# Whale_Lamp-base.net
KiCad netlist of a schematic drawn in EAGLE
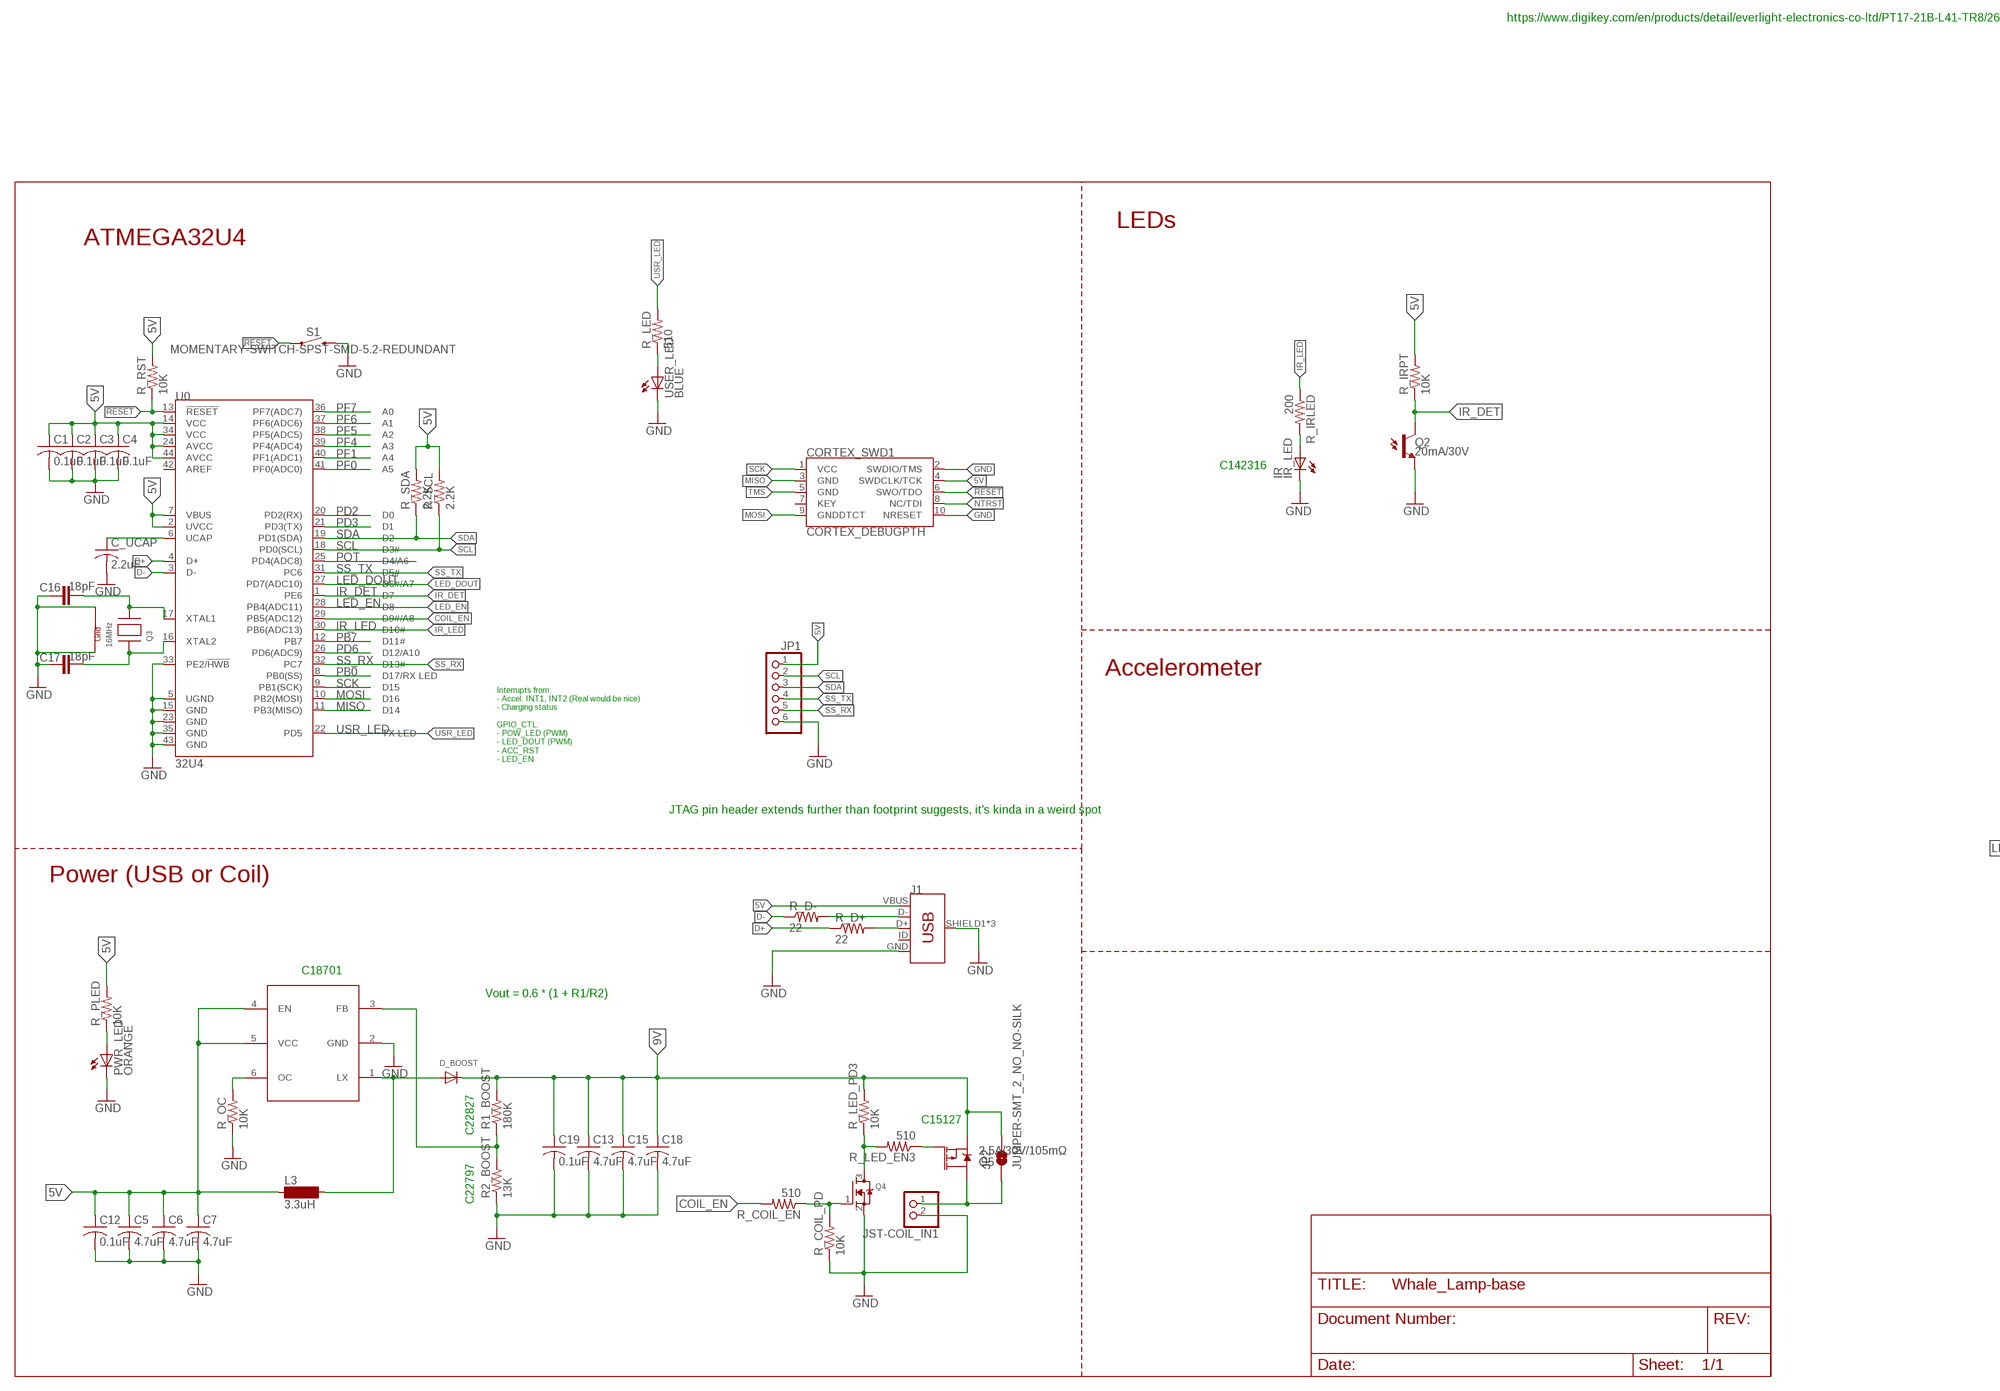
[diagram p0: schematic, sheet 1, part 1 of 2]
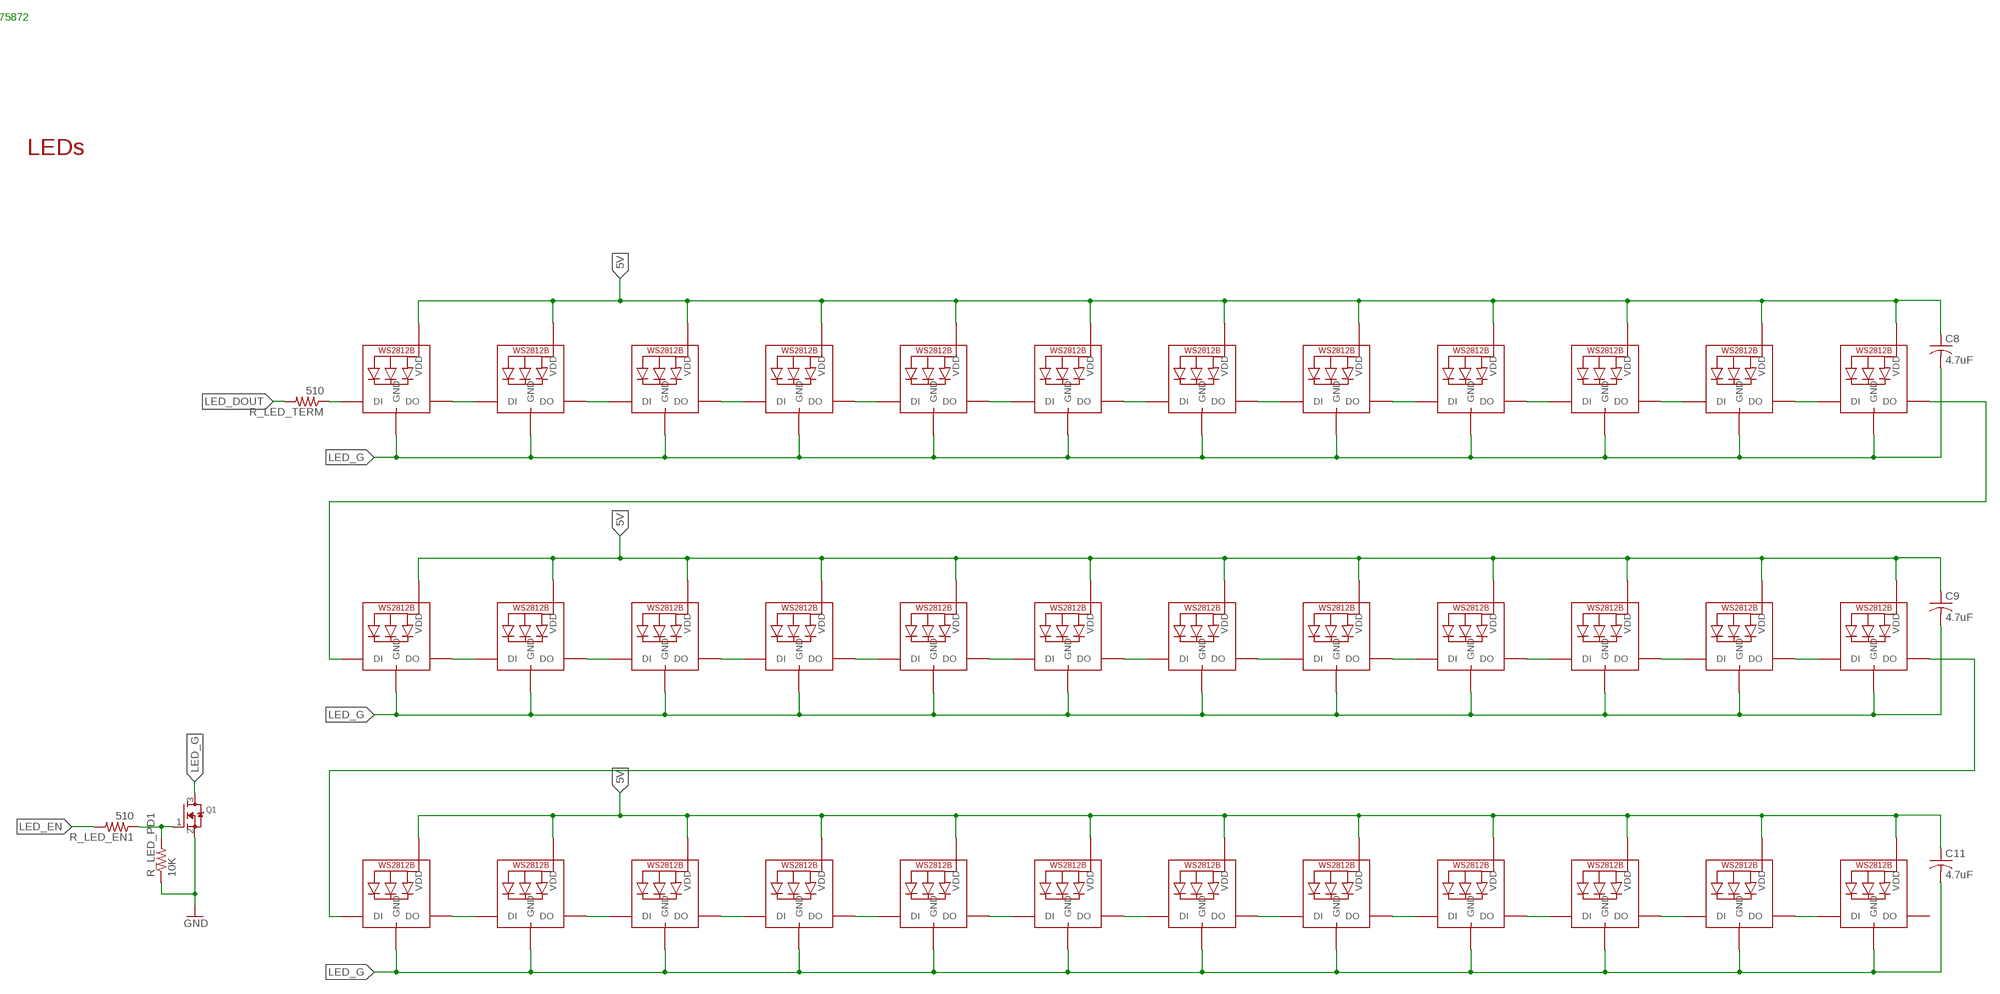
[diagram p1: schematic, sheet 1, part 2 of 2]

(export (version "E")
  (design (tool "Eeschema 10.0.6"))
  (components
    (comp (ref "C1")
      (value "0.1uF")
      (footprint "eagle-import:C0402")
      (libsource (lib "eagle-import") (part "C-USC0402"))
    )
    (comp (ref "C2")
      (value "0.1uF")
      (footprint "eagle-import:C0402")
      (libsource (lib "eagle-import") (part "C-USC0402"))
    )
    (comp (ref "C3")
      (value "0.1uF")
      (footprint "eagle-import:C0402")
      (libsource (lib "eagle-import") (part "C-USC0402"))
    )
    (comp (ref "C4")
      (value "0.1uF")
      (footprint "eagle-import:C0402")
      (libsource (lib "eagle-import") (part "C-USC0402"))
    )
    (comp (ref "C5")
      (value "4.7uF")
      (footprint "eagle-import:C0603")
      (libsource (lib "eagle-import") (part "C-USC0603"))
    )
    (comp (ref "C6")
      (value "4.7uF")
      (footprint "eagle-import:C0603")
      (libsource (lib "eagle-import") (part "C-USC0603"))
    )
    (comp (ref "C7")
      (value "4.7uF")
      (footprint "eagle-import:C0603")
      (libsource (lib "eagle-import") (part "C-USC0603"))
    )
    (comp (ref "C8")
      (value "4.7uF")
      (footprint "eagle-import:C0603")
      (libsource (lib "eagle-import") (part "C-USC0603"))
    )
    (comp (ref "C9")
      (value "4.7uF")
      (footprint "eagle-import:C0603")
      (libsource (lib "eagle-import") (part "C-USC0603"))
    )
    (comp (ref "C11")
      (value "4.7uF")
      (footprint "eagle-import:C0603")
      (libsource (lib "eagle-import") (part "C-USC0603"))
    )
    (comp (ref "C12")
      (value "0.1uF")
      (footprint "eagle-import:C0402")
      (libsource (lib "eagle-import") (part "C-USC0402"))
    )
    (comp (ref "C13")
      (value "4.7uF")
      (footprint "eagle-import:C0603")
      (libsource (lib "eagle-import") (part "C-USC0603"))
    )
    (comp (ref "C15")
      (value "4.7uF")
      (footprint "eagle-import:C0603")
      (libsource (lib "eagle-import") (part "C-USC0603"))
    )
    (comp (ref "C16")
      (value "18pF")
      (footprint "eagle-import:0402-CAP")
      (libsource (lib "eagle-import") (part "CAP0402-CAP"))
    )
    (comp (ref "C17")
      (value "18pF")
      (footprint "eagle-import:0402-CAP")
      (libsource (lib "eagle-import") (part "CAP0402-CAP"))
    )
    (comp (ref "C18")
      (value "4.7uF")
      (footprint "eagle-import:C0603")
      (libsource (lib "eagle-import") (part "C-USC0603"))
    )
    (comp (ref "C19")
      (value "0.1uF")
      (footprint "eagle-import:C0402")
      (libsource (lib "eagle-import") (part "C-USC0402"))
    )
    (comp (ref "CORTEX_SWD1")
      (value "CORTEX_DEBUGPTH")
      (footprint "eagle-import:2X5-PTH-1.27MM")
      (libsource (lib "eagle-import") (part "CORTEX_DEBUGPTH"))
    )
    (comp (ref "C_UCAP")
      (value "2.2uF")
      (footprint "eagle-import:C0603")
      (libsource (lib "eagle-import") (part "C-USC0603"))
    )
    (comp (ref "D_BOOST")
      (value "DIODESOD-123")
      (footprint "eagle-import:SOD-123")
      (libsource (lib "eagle-import") (part "DIODESOD-123"))
    )
    (comp (ref "FP6291")
      (value "FP6291")
      (footprint "eagle-import:SOT23-6L")
      (libsource (lib "eagle-import") (part "FP6291"))
    )
    (comp (ref "IR_LED")
      (value "IR")
      (footprint "eagle-import:CHIPLED_0603")
      (libsource (lib "eagle-import") (part "LEDCHIPLED_0603"))
    )
    (comp (ref "J1")
      (value "USB_MICRO-B_FEMALE-SMT")
      (footprint "eagle-import:USB-B-MICRO-SMD")
      (libsource (lib "eagle-import") (part "USB_MICRO-B_FEMALE-SMT"))
    )
    (comp (ref "JP1")
      (value "PINHD-1X6")
      (footprint "eagle-import:1X06")
      (libsource (lib "eagle-import") (part "PINHD-1X6"))
    )
    (comp (ref "JP2")
      (value "JUMPER-SMT_2_NO_NO-SILK")
      (footprint "eagle-import:SMT-JUMPER_2_NO_NO-SILK")
      (libsource (lib "eagle-import") (part "JUMPER-SMT_2_NO_NO-SILK"))
    )
    (comp (ref "JST-COIL_IN1")
      (value "JST_2PIN-THM-RA")
      (footprint "eagle-import:JST-PH-2-THM-RA")
      (libsource (lib "eagle-import") (part "JST_2PIN-THM-RA"))
    )
    (comp (ref "L3")
      (value "3.3uH")
      (footprint "eagle-import:MS50")
      (libsource (lib "eagle-import") (part "MS50"))
    )
    (comp (ref "LED1")
      (value "WS2812B_5050N")
      (footprint "eagle-import:WS2812B-NARROW")
      (libsource (lib "eagle-import") (part "WS2812B_5050N"))
    )
    (comp (ref "LED2")
      (value "WS2812B_5050N")
      (footprint "eagle-import:WS2812B-NARROW")
      (libsource (lib "eagle-import") (part "WS2812B_5050N"))
    )
    (comp (ref "LED3")
      (value "WS2812B_5050N")
      (footprint "eagle-import:WS2812B-NARROW")
      (libsource (lib "eagle-import") (part "WS2812B_5050N"))
    )
    (comp (ref "LED4")
      (value "WS2812B_5050N")
      (footprint "eagle-import:WS2812B-NARROW")
      (libsource (lib "eagle-import") (part "WS2812B_5050N"))
    )
    (comp (ref "LED5")
      (value "WS2812B_5050N")
      (footprint "eagle-import:WS2812B-NARROW")
      (libsource (lib "eagle-import") (part "WS2812B_5050N"))
    )
    (comp (ref "LED6")
      (value "WS2812B_5050N")
      (footprint "eagle-import:WS2812B-NARROW")
      (libsource (lib "eagle-import") (part "WS2812B_5050N"))
    )
    (comp (ref "LED7")
      (value "WS2812B_5050N")
      (footprint "eagle-import:WS2812B-NARROW")
      (libsource (lib "eagle-import") (part "WS2812B_5050N"))
    )
    (comp (ref "LED8")
      (value "WS2812B_5050N")
      (footprint "eagle-import:WS2812B-NARROW")
      (libsource (lib "eagle-import") (part "WS2812B_5050N"))
    )
    (comp (ref "LED9")
      (value "WS2812B_5050N")
      (footprint "eagle-import:WS2812B-NARROW")
      (libsource (lib "eagle-import") (part "WS2812B_5050N"))
    )
    (comp (ref "LED10")
      (value "WS2812B_5050N")
      (footprint "eagle-import:WS2812B-NARROW")
      (libsource (lib "eagle-import") (part "WS2812B_5050N"))
    )
    (comp (ref "LED11")
      (value "WS2812B_5050N")
      (footprint "eagle-import:WS2812B-NARROW")
      (libsource (lib "eagle-import") (part "WS2812B_5050N"))
    )
    (comp (ref "LED12")
      (value "WS2812B_5050N")
      (footprint "eagle-import:WS2812B-NARROW")
      (libsource (lib "eagle-import") (part "WS2812B_5050N"))
    )
    (comp (ref "LED13")
      (value "WS2812B_5050N")
      (footprint "eagle-import:WS2812B-NARROW")
      (libsource (lib "eagle-import") (part "WS2812B_5050N"))
    )
    (comp (ref "LED14")
      (value "WS2812B_5050N")
      (footprint "eagle-import:WS2812B-NARROW")
      (libsource (lib "eagle-import") (part "WS2812B_5050N"))
    )
    (comp (ref "LED15")
      (value "WS2812B_5050N")
      (footprint "eagle-import:WS2812B-NARROW")
      (libsource (lib "eagle-import") (part "WS2812B_5050N"))
    )
    (comp (ref "LED16")
      (value "WS2812B_5050N")
      (footprint "eagle-import:WS2812B-NARROW")
      (libsource (lib "eagle-import") (part "WS2812B_5050N"))
    )
    (comp (ref "LED17")
      (value "WS2812B_5050N")
      (footprint "eagle-import:WS2812B-NARROW")
      (libsource (lib "eagle-import") (part "WS2812B_5050N"))
    )
    (comp (ref "LED18")
      (value "WS2812B_5050N")
      (footprint "eagle-import:WS2812B-NARROW")
      (libsource (lib "eagle-import") (part "WS2812B_5050N"))
    )
    (comp (ref "LED19")
      (value "WS2812B_5050N")
      (footprint "eagle-import:WS2812B-NARROW")
      (libsource (lib "eagle-import") (part "WS2812B_5050N"))
    )
    (comp (ref "LED20")
      (value "WS2812B_5050N")
      (footprint "eagle-import:WS2812B-NARROW")
      (libsource (lib "eagle-import") (part "WS2812B_5050N"))
    )
    (comp (ref "LED21")
      (value "WS2812B_5050N")
      (footprint "eagle-import:WS2812B-NARROW")
      (libsource (lib "eagle-import") (part "WS2812B_5050N"))
    )
    (comp (ref "LED22")
      (value "WS2812B_5050N")
      (footprint "eagle-import:WS2812B-NARROW")
      (libsource (lib "eagle-import") (part "WS2812B_5050N"))
    )
    (comp (ref "LED23")
      (value "WS2812B_5050N")
      (footprint "eagle-import:WS2812B-NARROW")
      (libsource (lib "eagle-import") (part "WS2812B_5050N"))
    )
    (comp (ref "LED24")
      (value "WS2812B_5050N")
      (footprint "eagle-import:WS2812B-NARROW")
      (libsource (lib "eagle-import") (part "WS2812B_5050N"))
    )
    (comp (ref "LED25")
      (value "WS2812B_5050N")
      (footprint "eagle-import:WS2812B-NARROW")
      (libsource (lib "eagle-import") (part "WS2812B_5050N"))
    )
    (comp (ref "LED26")
      (value "WS2812B_5050N")
      (footprint "eagle-import:WS2812B-NARROW")
      (libsource (lib "eagle-import") (part "WS2812B_5050N"))
    )
    (comp (ref "LED27")
      (value "WS2812B_5050N")
      (footprint "eagle-import:WS2812B-NARROW")
      (libsource (lib "eagle-import") (part "WS2812B_5050N"))
    )
    (comp (ref "LED28")
      (value "WS2812B_5050N")
      (footprint "eagle-import:WS2812B-NARROW")
      (libsource (lib "eagle-import") (part "WS2812B_5050N"))
    )
    (comp (ref "LED29")
      (value "WS2812B_5050N")
      (footprint "eagle-import:WS2812B-NARROW")
      (libsource (lib "eagle-import") (part "WS2812B_5050N"))
    )
    (comp (ref "LED30")
      (value "WS2812B_5050N")
      (footprint "eagle-import:WS2812B-NARROW")
      (libsource (lib "eagle-import") (part "WS2812B_5050N"))
    )
    (comp (ref "LED31")
      (value "WS2812B_5050N")
      (footprint "eagle-import:WS2812B-NARROW")
      (libsource (lib "eagle-import") (part "WS2812B_5050N"))
    )
    (comp (ref "LED32")
      (value "WS2812B_5050N")
      (footprint "eagle-import:WS2812B-NARROW")
      (libsource (lib "eagle-import") (part "WS2812B_5050N"))
    )
    (comp (ref "LED33")
      (value "WS2812B_5050N")
      (footprint "eagle-import:WS2812B-NARROW")
      (libsource (lib "eagle-import") (part "WS2812B_5050N"))
    )
    (comp (ref "LED34")
      (value "WS2812B_5050N")
      (footprint "eagle-import:WS2812B-NARROW")
      (libsource (lib "eagle-import") (part "WS2812B_5050N"))
    )
    (comp (ref "LED35")
      (value "WS2812B_5050N")
      (footprint "eagle-import:WS2812B-NARROW")
      (libsource (lib "eagle-import") (part "WS2812B_5050N"))
    )
    (comp (ref "LED36")
      (value "WS2812B_5050N")
      (footprint "eagle-import:WS2812B-NARROW")
      (libsource (lib "eagle-import") (part "WS2812B_5050N"))
    )
    (comp (ref "PWR_LED")
      (value "ORANGE")
      (footprint "eagle-import:CHIPLED_0603")
      (libsource (lib "eagle-import") (part "LEDCHIPLED_0603"))
    )
    (comp (ref "Q1")
      (value "MOSFET-NREFLOW")
      (footprint "eagle-import:SOT23")
      (libsource (lib "eagle-import") (part "MOSFET-NREFLOW"))
    )
    (comp (ref "Q2")
      (value "20mA/30V")
      (footprint "eagle-import:PT17-21C-L41-TR8")
      (libsource (lib "eagle-import") (part "PHOTOTRANSISTORPT17-21C-L41-TR8"))
    )
    (comp (ref "Q3")
      (value "16MHz")
      (footprint "eagle-import:NX3225")
      (libsource (lib "eagle-import") (part "XTAL-4-3225"))
    )
    (comp (ref "Q4")
      (value "MOSFET-NREFLOW")
      (footprint "eagle-import:SOT23")
      (libsource (lib "eagle-import") (part "MOSFET-NREFLOW"))
    )
    (comp (ref "Q5")
      (value "2.5A/30V/105mΩ")
      (footprint "eagle-import:SOT23-3")
      (libsource (lib "eagle-import") (part "MOSFET_PCH-DMG2307L"))
    )
    (comp (ref "R1_BOOST")
      (value "180K")
      (footprint "eagle-import:R0603")
      (libsource (lib "eagle-import") (part "adafruit_420_R-US_R0603"))
    )
    (comp (ref "R2_BOOST")
      (value "13K")
      (footprint "eagle-import:R0603")
      (libsource (lib "eagle-import") (part "adafruit_420_R-US_R0603"))
    )
    (comp (ref "R_COIL_EN")
      (value "510")
      (footprint "eagle-import:R0402")
      (libsource (lib "eagle-import") (part "R-US_R0402"))
    )
    (comp (ref "R_COIL_PD")
      (value "10K")
      (footprint "eagle-import:R0402")
      (libsource (lib "eagle-import") (part "R-US_R0402"))
    )
    (comp (ref "R_D+")
      (value "22")
      (footprint "eagle-import:R0402")
      (libsource (lib "eagle-import") (part "R-US_R0402"))
    )
    (comp (ref "R_D-")
      (value "22")
      (footprint "eagle-import:R0402")
      (libsource (lib "eagle-import") (part "R-US_R0402"))
    )
    (comp (ref "R_IRLED")
      (value "200")
      (footprint "eagle-import:R0603")
      (libsource (lib "eagle-import") (part "R-US_R0603"))
    )
    (comp (ref "R_IRPT")
      (value "10K")
      (footprint "eagle-import:R0402")
      (libsource (lib "eagle-import") (part "R-US_R0402"))
    )
    (comp (ref "R_LED")
      (value "510")
      (footprint "eagle-import:R0402")
      (libsource (lib "eagle-import") (part "R-US_R0402"))
    )
    (comp (ref "R_LED_EN1")
      (value "510")
      (footprint "eagle-import:R0402")
      (libsource (lib "eagle-import") (part "R-US_R0402"))
    )
    (comp (ref "R_LED_EN3")
      (value "510")
      (footprint "eagle-import:R0402")
      (libsource (lib "eagle-import") (part "R-US_R0402"))
    )
    (comp (ref "R_LED_PD1")
      (value "10K")
      (footprint "eagle-import:R0402")
      (libsource (lib "eagle-import") (part "R-US_R0402"))
    )
    (comp (ref "R_LED_PD3")
      (value "10K")
      (footprint "eagle-import:R0402")
      (libsource (lib "eagle-import") (part "R-US_R0402"))
    )
    (comp (ref "R_LED_TERM")
      (value "510")
      (footprint "eagle-import:R0402")
      (libsource (lib "eagle-import") (part "R-US_R0402"))
    )
    (comp (ref "R_OC")
      (value "10K")
      (footprint "eagle-import:R0402")
      (libsource (lib "eagle-import") (part "R-US_R0402"))
    )
    (comp (ref "R_PLED")
      (value "10K")
      (footprint "eagle-import:R0402")
      (libsource (lib "eagle-import") (part "R-US_R0402"))
    )
    (comp (ref "R_RST")
      (value "10K")
      (footprint "eagle-import:R0402")
      (libsource (lib "eagle-import") (part "R-US_R0402"))
    )
    (comp (ref "R_SCL")
      (value "2.2K")
      (footprint "eagle-import:R0402")
      (libsource (lib "eagle-import") (part "R-US_R0402"))
    )
    (comp (ref "R_SDA")
      (value "2.2K")
      (footprint "eagle-import:R0402")
      (libsource (lib "eagle-import") (part "R-US_R0402"))
    )
    (comp (ref "S1")
      (value "MOMENTARY-SWITCH-SPST-SMD-5.2-REDUNDANT")
      (footprint "eagle-import:TACTILE_SWITCH_SMD_5.2MM")
      (libsource (lib "eagle-import") (part "MOMENTARY-SWITCH-SPST-SMD-5.2-REDUNDANT"))
    )
    (comp (ref "U0")
      (value "32U4")
      (footprint "eagle-import:QFN-44")
      (libsource (lib "eagle-import") (part "ATMEGA32U4QFN"))
    )
    (comp (ref "USER_LED")
      (value "BLUE")
      (footprint "eagle-import:CHIPLED_0603")
      (libsource (lib "eagle-import") (part "LEDCHIPLED_0603"))
    )
  )
  (nets
    (net (code "1") (name "/PB0") (class "Default")
      (node (ref "U0") (pin "8") (pinfunction "PB0(SS)_8") (pintype "bidirectional"))
    )
    (net (code "2") (name "/PB7") (class "Default")
      (node (ref "U0") (pin "12") (pinfunction "PB7_12") (pintype "bidirectional"))
    )
    (net (code "3") (name "/PD2") (class "Default")
      (node (ref "U0") (pin "20") (pinfunction "PD2(RX)_20") (pintype "bidirectional"))
    )
    (net (code "4") (name "/PD3") (class "Default")
      (node (ref "U0") (pin "21") (pinfunction "PD3(TX)_21") (pintype "bidirectional"))
    )
    (net (code "5") (name "/PD6") (class "Default")
      (node (ref "U0") (pin "26") (pinfunction "PD6(ADC9)_26") (pintype "bidirectional"))
    )
    (net (code "6") (name "/PF0") (class "Default")
      (node (ref "U0") (pin "41") (pinfunction "PF0(ADC0)_41") (pintype "bidirectional"))
    )
    (net (code "7") (name "/PF1") (class "Default")
      (node (ref "U0") (pin "40") (pinfunction "PF1(ADC1)_40") (pintype "bidirectional"))
    )
    (net (code "8") (name "/PF4") (class "Default")
      (node (ref "U0") (pin "39") (pinfunction "PF4(ADC4)_39") (pintype "bidirectional"))
    )
    (net (code "9") (name "/PF5") (class "Default")
      (node (ref "U0") (pin "38") (pinfunction "PF5(ADC5)_38") (pintype "bidirectional"))
    )
    (net (code "10") (name "/PF6") (class "Default")
      (node (ref "U0") (pin "37") (pinfunction "PF6(ADC6)_37") (pintype "bidirectional"))
    )
    (net (code "11") (name "/PF7") (class "Default")
      (node (ref "U0") (pin "36") (pinfunction "PF7(ADC7)_36") (pintype "bidirectional"))
    )
    (net (code "12") (name "/POT") (class "Default")
      (node (ref "U0") (pin "25") (pinfunction "PD4(ADC8)_25") (pintype "bidirectional"))
    )
    (net (code "13") (name "/~{RESET}") (class "Default")
      (node (ref "CORTEX_SWD1") (pin "6") (pinfunction "SWO/TDO_6") (pintype "bidirectional"))
      (node (ref "R_RST") (pin "1") (pinfunction "1_1") (pintype "passive"))
      (node (ref "S1") (pin "1") (pinfunction "1_1") (pintype "passive"))
      (node (ref "S1") (pin "2") (pinfunction "1_2") (pintype "passive"))
      (node (ref "U0") (pin "13") (pinfunction "~{RESET}_13") (pintype "bidirectional"))
    )
    (net (code "14") (name "5V") (class "Default")
      (node (ref "C1") (pin "1") (pinfunction "1_1") (pintype "passive"))
      (node (ref "C11") (pin "1") (pinfunction "1_1") (pintype "passive"))
      (node (ref "C12") (pin "1") (pinfunction "1_1") (pintype "passive"))
      (node (ref "C2") (pin "1") (pinfunction "1_1") (pintype "passive"))
      (node (ref "C3") (pin "1") (pinfunction "1_1") (pintype "passive"))
      (node (ref "C4") (pin "1") (pinfunction "1_1") (pintype "passive"))
      (node (ref "C5") (pin "1") (pinfunction "1_1") (pintype "passive"))
      (node (ref "C6") (pin "1") (pinfunction "1_1") (pintype "passive"))
      (node (ref "C7") (pin "1") (pinfunction "1_1") (pintype "passive"))
      (node (ref "C8") (pin "1") (pinfunction "1_1") (pintype "passive"))
      (node (ref "C9") (pin "1") (pinfunction "1_1") (pintype "passive"))
      (node (ref "CORTEX_SWD1") (pin "4") (pinfunction "SWDCLK/TCK_4") (pintype "bidirectional"))
      (node (ref "FP6291") (pin "4") (pinfunction "EN_4") (pintype "bidirectional"))
      (node (ref "FP6291") (pin "5") (pinfunction "VCC_5") (pintype "bidirectional"))
      (node (ref "J1") (pin "VBUS") (pinfunction "VBUS_VBUS") (pintype "power_in"))
      (node (ref "JP1") (pin "1") (pinfunction "1_1") (pintype "passive"))
      (node (ref "L3") (pin "1") (pinfunction "1_1") (pintype "passive"))
      (node (ref "LED1") (pin "1-VDD") (pinfunction "VDD_1-VDD") (pintype "power_in"))
      (node (ref "LED10") (pin "1-VDD") (pinfunction "VDD_1-VDD") (pintype "power_in"))
      (node (ref "LED11") (pin "1-VDD") (pinfunction "VDD_1-VDD") (pintype "power_in"))
      (node (ref "LED12") (pin "1-VDD") (pinfunction "VDD_1-VDD") (pintype "power_in"))
      (node (ref "LED13") (pin "1-VDD") (pinfunction "VDD_1-VDD") (pintype "power_in"))
      (node (ref "LED14") (pin "1-VDD") (pinfunction "VDD_1-VDD") (pintype "power_in"))
      (node (ref "LED15") (pin "1-VDD") (pinfunction "VDD_1-VDD") (pintype "power_in"))
      (node (ref "LED16") (pin "1-VDD") (pinfunction "VDD_1-VDD") (pintype "power_in"))
      (node (ref "LED17") (pin "1-VDD") (pinfunction "VDD_1-VDD") (pintype "power_in"))
      (node (ref "LED18") (pin "1-VDD") (pinfunction "VDD_1-VDD") (pintype "power_in"))
      (node (ref "LED19") (pin "1-VDD") (pinfunction "VDD_1-VDD") (pintype "power_in"))
      (node (ref "LED2") (pin "1-VDD") (pinfunction "VDD_1-VDD") (pintype "power_in"))
      (node (ref "LED20") (pin "1-VDD") (pinfunction "VDD_1-VDD") (pintype "power_in"))
      (node (ref "LED21") (pin "1-VDD") (pinfunction "VDD_1-VDD") (pintype "power_in"))
      (node (ref "LED22") (pin "1-VDD") (pinfunction "VDD_1-VDD") (pintype "power_in"))
      (node (ref "LED23") (pin "1-VDD") (pinfunction "VDD_1-VDD") (pintype "power_in"))
      (node (ref "LED24") (pin "1-VDD") (pinfunction "VDD_1-VDD") (pintype "power_in"))
      (node (ref "LED25") (pin "1-VDD") (pinfunction "VDD_1-VDD") (pintype "power_in"))
      (node (ref "LED26") (pin "1-VDD") (pinfunction "VDD_1-VDD") (pintype "power_in"))
      (node (ref "LED27") (pin "1-VDD") (pinfunction "VDD_1-VDD") (pintype "power_in"))
      (node (ref "LED28") (pin "1-VDD") (pinfunction "VDD_1-VDD") (pintype "power_in"))
      (node (ref "LED29") (pin "1-VDD") (pinfunction "VDD_1-VDD") (pintype "power_in"))
      (node (ref "LED3") (pin "1-VDD") (pinfunction "VDD_1-VDD") (pintype "power_in"))
      (node (ref "LED30") (pin "1-VDD") (pinfunction "VDD_1-VDD") (pintype "power_in"))
      (node (ref "LED31") (pin "1-VDD") (pinfunction "VDD_1-VDD") (pintype "power_in"))
      (node (ref "LED32") (pin "1-VDD") (pinfunction "VDD_1-VDD") (pintype "power_in"))
      (node (ref "LED33") (pin "1-VDD") (pinfunction "VDD_1-VDD") (pintype "power_in"))
      (node (ref "LED34") (pin "1-VDD") (pinfunction "VDD_1-VDD") (pintype "power_in"))
      (node (ref "LED35") (pin "1-VDD") (pinfunction "VDD_1-VDD") (pintype "power_in"))
      (node (ref "LED36") (pin "1-VDD") (pinfunction "VDD_1-VDD") (pintype "power_in"))
      (node (ref "LED4") (pin "1-VDD") (pinfunction "VDD_1-VDD") (pintype "power_in"))
      (node (ref "LED5") (pin "1-VDD") (pinfunction "VDD_1-VDD") (pintype "power_in"))
      (node (ref "LED6") (pin "1-VDD") (pinfunction "VDD_1-VDD") (pintype "power_in"))
      (node (ref "LED7") (pin "1-VDD") (pinfunction "VDD_1-VDD") (pintype "power_in"))
      (node (ref "LED8") (pin "1-VDD") (pinfunction "VDD_1-VDD") (pintype "power_in"))
      (node (ref "LED9") (pin "1-VDD") (pinfunction "VDD_1-VDD") (pintype "power_in"))
      (node (ref "R_IRPT") (pin "2") (pinfunction "2_2") (pintype "passive"))
      (node (ref "R_PLED") (pin "2") (pinfunction "2_2") (pintype "passive"))
      (node (ref "R_RST") (pin "2") (pinfunction "2_2") (pintype "passive"))
      (node (ref "R_SCL") (pin "2") (pinfunction "2_2") (pintype "passive"))
      (node (ref "R_SDA") (pin "2") (pinfunction "2_2") (pintype "passive"))
      (node (ref "U0") (pin "14") (pinfunction "VCC_14") (pintype "bidirectional"))
      (node (ref "U0") (pin "2") (pinfunction "UVCC_2") (pintype "bidirectional"))
      (node (ref "U0") (pin "24") (pinfunction "AVCC_24") (pintype "bidirectional"))
      (node (ref "U0") (pin "34") (pinfunction "VCC_34") (pintype "bidirectional"))
      (node (ref "U0") (pin "44") (pinfunction "AVCC_44") (pintype "bidirectional"))
      (node (ref "U0") (pin "7") (pinfunction "VBUS_7") (pintype "bidirectional"))
    )
    (net (code "15") (name "9V") (class "Default")
      (node (ref "C13") (pin "1") (pinfunction "1_1") (pintype "passive"))
      (node (ref "C15") (pin "1") (pinfunction "1_1") (pintype "passive"))
      (node (ref "C18") (pin "1") (pinfunction "1_1") (pintype "passive"))
      (node (ref "C19") (pin "1") (pinfunction "1_1") (pintype "passive"))
      (node (ref "D_BOOST") (pin "C") (pinfunction "C_C") (pintype "passive"))
      (node (ref "JP2") (pin "2") (pinfunction "2_2") (pintype "passive"))
      (node (ref "Q5") (pin "2") (pinfunction "S_2") (pintype "bidirectional"))
      (node (ref "R1_BOOST") (pin "2") (pinfunction "2_2") (pintype "passive"))
      (node (ref "R_LED_PD3") (pin "2") (pinfunction "2_2") (pintype "passive"))
    )
    (net (code "16") (name "COIL_EN") (class "Default")
      (node (ref "R_COIL_EN") (pin "2") (pinfunction "2_2") (pintype "passive"))
      (node (ref "U0") (pin "29") (pinfunction "PB5(ADC12)_29") (pintype "bidirectional"))
    )
    (net (code "17") (name "D+") (class "Default")
      (node (ref "R_D+") (pin "1") (pinfunction "1_1") (pintype "passive"))
      (node (ref "U0") (pin "4") (pinfunction "D+_4") (pintype "bidirectional"))
    )
    (net (code "18") (name "D-") (class "Default")
      (node (ref "R_D-") (pin "1") (pinfunction "1_1") (pintype "passive"))
      (node (ref "U0") (pin "3") (pinfunction "D-_3") (pintype "bidirectional"))
    )
    (net (code "19") (name "GND") (class "Default")
      (node (ref "C1") (pin "2") (pinfunction "2_2") (pintype "passive"))
      (node (ref "C12") (pin "2") (pinfunction "2_2") (pintype "passive"))
      (node (ref "C13") (pin "2") (pinfunction "2_2") (pintype "passive"))
      (node (ref "C15") (pin "2") (pinfunction "2_2") (pintype "passive"))
      (node (ref "C16") (pin "1") (pinfunction "1_1") (pintype "passive"))
      (node (ref "C17") (pin "1") (pinfunction "1_1") (pintype "passive"))
      (node (ref "C18") (pin "2") (pinfunction "2_2") (pintype "passive"))
      (node (ref "C19") (pin "2") (pinfunction "2_2") (pintype "passive"))
      (node (ref "C2") (pin "2") (pinfunction "2_2") (pintype "passive"))
      (node (ref "C3") (pin "2") (pinfunction "2_2") (pintype "passive"))
      (node (ref "C4") (pin "2") (pinfunction "2_2") (pintype "passive"))
      (node (ref "C5") (pin "2") (pinfunction "2_2") (pintype "passive"))
      (node (ref "C6") (pin "2") (pinfunction "2_2") (pintype "passive"))
      (node (ref "C7") (pin "2") (pinfunction "2_2") (pintype "passive"))
      (node (ref "CORTEX_SWD1") (pin "10") (pinfunction "NRESET_10") (pintype "bidirectional"))
      (node (ref "CORTEX_SWD1") (pin "2") (pinfunction "SWDIO/TMS_2") (pintype "bidirectional"))
      (node (ref "C_UCAP") (pin "2") (pinfunction "2_2") (pintype "passive"))
      (node (ref "FP6291") (pin "2") (pinfunction "GND_2") (pintype "bidirectional"))
      (node (ref "IR_LED") (pin "C") (pinfunction "C_C") (pintype "passive"))
      (node (ref "J1") (pin "GND") (pinfunction "GND_GND") (pintype "power_in"))
      (node (ref "J1") (pin "SHIELD1") (pinfunction "SHIELD_SHIELD1") (pintype "bidirectional"))
      (node (ref "J1") (pin "SHIELD2") (pinfunction "SHIELD_SHIELD2") (pintype "bidirectional"))
      (node (ref "J1") (pin "SHIELD3") (pinfunction "SHIELD_SHIELD3") (pintype "bidirectional"))
      (node (ref "JP1") (pin "6") (pinfunction "6_6") (pintype "passive"))
      (node (ref "JST-COIL_IN1") (pin "2") (pinfunction "1_2") (pintype "passive"))
      (node (ref "PWR_LED") (pin "C") (pinfunction "C_C") (pintype "passive"))
      (node (ref "Q1") (pin "2") (pinfunction "S_2") (pintype "bidirectional"))
      (node (ref "Q2") (pin "E") (pinfunction "E_E") (pintype "passive"))
      (node (ref "Q3") (pin "2") (pinfunction "G2_2") (pintype "power_in"))
      (node (ref "Q3") (pin "4") (pinfunction "G1_4") (pintype "power_in"))
      (node (ref "Q4") (pin "2") (pinfunction "S_2") (pintype "bidirectional"))
      (node (ref "R2_BOOST") (pin "1") (pinfunction "1_1") (pintype "passive"))
      (node (ref "R_COIL_PD") (pin "1") (pinfunction "1_1") (pintype "passive"))
      (node (ref "R_LED_PD1") (pin "1") (pinfunction "1_1") (pintype "passive"))
      (node (ref "R_OC") (pin "1") (pinfunction "1_1") (pintype "passive"))
      (node (ref "S1") (pin "3") (pinfunction "2_3") (pintype "passive"))
      (node (ref "S1") (pin "4") (pinfunction "2_4") (pintype "passive"))
      (node (ref "U0") (pin "15") (pinfunction "GND_15") (pintype "bidirectional"))
      (node (ref "U0") (pin "23") (pinfunction "GND_23") (pintype "bidirectional"))
      (node (ref "U0") (pin "33") (pinfunction "PE2/~{HWB}_33") (pintype "bidirectional"))
      (node (ref "U0") (pin "35") (pinfunction "GND_35") (pintype "bidirectional"))
      (node (ref "U0") (pin "43") (pinfunction "GND_43") (pintype "bidirectional"))
      (node (ref "U0") (pin "5") (pinfunction "UGND_5") (pintype "bidirectional"))
      (node (ref "USER_LED") (pin "C") (pinfunction "C_C") (pintype "passive"))
    )
    (net (code "20") (name "IR_DET") (class "Default")
      (node (ref "Q2") (pin "C") (pinfunction "C_C") (pintype "passive"))
      (node (ref "R_IRPT") (pin "1") (pinfunction "1_1") (pintype "passive"))
      (node (ref "U0") (pin "1") (pinfunction "PE6_1") (pintype "bidirectional"))
    )
    (net (code "21") (name "IR_LED") (class "Default")
      (node (ref "R_IRLED") (pin "1") (pinfunction "1_1") (pintype "passive"))
      (node (ref "U0") (pin "30") (pinfunction "PB6(ADC13)_30") (pintype "bidirectional"))
    )
    (net (code "22") (name "LED_DOUT") (class "Default")
      (node (ref "R_LED_TERM") (pin "2") (pinfunction "2_2") (pintype "passive"))
      (node (ref "U0") (pin "27") (pinfunction "PD7(ADC10)_27") (pintype "bidirectional"))
    )
    (net (code "23") (name "LED_EN") (class "Default")
      (node (ref "R_LED_EN1") (pin "2") (pinfunction "2_2") (pintype "passive"))
      (node (ref "U0") (pin "28") (pinfunction "PB4(ADC11)_28") (pintype "bidirectional"))
    )
    (net (code "24") (name "LED_G") (class "Default")
      (node (ref "C11") (pin "2") (pinfunction "2_2") (pintype "passive"))
      (node (ref "C8") (pin "2") (pinfunction "2_2") (pintype "passive"))
      (node (ref "C9") (pin "2") (pinfunction "2_2") (pintype "passive"))
      (node (ref "LED1") (pin "3-GND") (pinfunction "GND_3-GND") (pintype "power_in"))
      (node (ref "LED10") (pin "3-GND") (pinfunction "GND_3-GND") (pintype "power_in"))
      (node (ref "LED11") (pin "3-GND") (pinfunction "GND_3-GND") (pintype "power_in"))
      (node (ref "LED12") (pin "3-GND") (pinfunction "GND_3-GND") (pintype "power_in"))
      (node (ref "LED13") (pin "3-GND") (pinfunction "GND_3-GND") (pintype "power_in"))
      (node (ref "LED14") (pin "3-GND") (pinfunction "GND_3-GND") (pintype "power_in"))
      (node (ref "LED15") (pin "3-GND") (pinfunction "GND_3-GND") (pintype "power_in"))
      (node (ref "LED16") (pin "3-GND") (pinfunction "GND_3-GND") (pintype "power_in"))
      (node (ref "LED17") (pin "3-GND") (pinfunction "GND_3-GND") (pintype "power_in"))
      (node (ref "LED18") (pin "3-GND") (pinfunction "GND_3-GND") (pintype "power_in"))
      (node (ref "LED19") (pin "3-GND") (pinfunction "GND_3-GND") (pintype "power_in"))
      (node (ref "LED2") (pin "3-GND") (pinfunction "GND_3-GND") (pintype "power_in"))
      (node (ref "LED20") (pin "3-GND") (pinfunction "GND_3-GND") (pintype "power_in"))
      (node (ref "LED21") (pin "3-GND") (pinfunction "GND_3-GND") (pintype "power_in"))
      (node (ref "LED22") (pin "3-GND") (pinfunction "GND_3-GND") (pintype "power_in"))
      (node (ref "LED23") (pin "3-GND") (pinfunction "GND_3-GND") (pintype "power_in"))
      (node (ref "LED24") (pin "3-GND") (pinfunction "GND_3-GND") (pintype "power_in"))
      (node (ref "LED25") (pin "3-GND") (pinfunction "GND_3-GND") (pintype "power_in"))
      (node (ref "LED26") (pin "3-GND") (pinfunction "GND_3-GND") (pintype "power_in"))
      (node (ref "LED27") (pin "3-GND") (pinfunction "GND_3-GND") (pintype "power_in"))
      (node (ref "LED28") (pin "3-GND") (pinfunction "GND_3-GND") (pintype "power_in"))
      (node (ref "LED29") (pin "3-GND") (pinfunction "GND_3-GND") (pintype "power_in"))
      (node (ref "LED3") (pin "3-GND") (pinfunction "GND_3-GND") (pintype "power_in"))
      (node (ref "LED30") (pin "3-GND") (pinfunction "GND_3-GND") (pintype "power_in"))
      (node (ref "LED31") (pin "3-GND") (pinfunction "GND_3-GND") (pintype "power_in"))
      (node (ref "LED32") (pin "3-GND") (pinfunction "GND_3-GND") (pintype "power_in"))
      (node (ref "LED33") (pin "3-GND") (pinfunction "GND_3-GND") (pintype "power_in"))
      (node (ref "LED34") (pin "3-GND") (pinfunction "GND_3-GND") (pintype "power_in"))
      (node (ref "LED35") (pin "3-GND") (pinfunction "GND_3-GND") (pintype "power_in"))
      (node (ref "LED36") (pin "3-GND") (pinfunction "GND_3-GND") (pintype "power_in"))
      (node (ref "LED4") (pin "3-GND") (pinfunction "GND_3-GND") (pintype "power_in"))
      (node (ref "LED5") (pin "3-GND") (pinfunction "GND_3-GND") (pintype "power_in"))
      (node (ref "LED6") (pin "3-GND") (pinfunction "GND_3-GND") (pintype "power_in"))
      (node (ref "LED7") (pin "3-GND") (pinfunction "GND_3-GND") (pintype "power_in"))
      (node (ref "LED8") (pin "3-GND") (pinfunction "GND_3-GND") (pintype "power_in"))
      (node (ref "LED9") (pin "3-GND") (pinfunction "GND_3-GND") (pintype "power_in"))
      (node (ref "Q1") (pin "3") (pinfunction "D_3") (pintype "bidirectional"))
    )
    (net (code "25") (name "MISO") (class "Default")
      (node (ref "CORTEX_SWD1") (pin "3") (pinfunction "GND_3") (pintype "bidirectional"))
      (node (ref "U0") (pin "11") (pinfunction "PB3(MISO)_11") (pintype "bidirectional"))
    )
    (net (code "26") (name "MOSI") (class "Default")
      (node (ref "CORTEX_SWD1") (pin "9") (pinfunction "GNDDTCT_9") (pintype "bidirectional"))
      (node (ref "U0") (pin "10") (pinfunction "PB2(MOSI)_10") (pintype "bidirectional"))
    )
    (net (code "27") (name "NTRST") (class "Default")
      (node (ref "CORTEX_SWD1") (pin "8") (pinfunction "NC/TDI_8") (pintype "bidirectional"))
    )
    (net (code "28") (name "Net-(FP6291-FB)") (class "Default")
      (node (ref "FP6291") (pin "3") (pinfunction "FB_3") (pintype "bidirectional"))
      (node (ref "R1_BOOST") (pin "1") (pinfunction "1_1") (pintype "passive"))
      (node (ref "R2_BOOST") (pin "2") (pinfunction "2_2") (pintype "passive"))
    )
    (net (code "29") (name "Net-(FP6291-LX)") (class "Default")
      (node (ref "D_BOOST") (pin "A") (pinfunction "A_A") (pintype "passive"))
      (node (ref "FP6291") (pin "1") (pinfunction "LX_1") (pintype "bidirectional"))
      (node (ref "L3") (pin "2") (pinfunction "2_2") (pintype "passive"))
    )
    (net (code "30") (name "Net-(FP6291-OC)") (class "Default")
      (node (ref "FP6291") (pin "6") (pinfunction "OC_6") (pintype "bidirectional"))
      (node (ref "R_OC") (pin "2") (pinfunction "2_2") (pintype "passive"))
    )
    (net (code "31") (name "Net-(IR_LED-PadA)") (class "Default")
      (node (ref "IR_LED") (pin "A") (pinfunction "A_A") (pintype "passive"))
      (node (ref "R_IRLED") (pin "2") (pinfunction "2_2") (pintype "passive"))
    )
    (net (code "32") (name "Net-(J1-PadD+)") (class "Default")
      (node (ref "J1") (pin "D+") (pinfunction "D+_D+") (pintype "bidirectional"))
      (node (ref "R_D+") (pin "2") (pinfunction "2_2") (pintype "passive"))
    )
    (net (code "33") (name "Net-(J1-PadD-)") (class "Default")
      (node (ref "J1") (pin "D-") (pinfunction "D-_D-") (pintype "bidirectional"))
      (node (ref "R_D-") (pin "2") (pinfunction "2_2") (pintype "passive"))
    )
    (net (code "34") (name "Net-(JST-COIL_IN1-2)") (class "Default")
      (node (ref "JP2") (pin "1") (pinfunction "1_1") (pintype "passive"))
      (node (ref "JST-COIL_IN1") (pin "1") (pinfunction "2_1") (pintype "passive"))
      (node (ref "Q5") (pin "3") (pinfunction "D_3") (pintype "bidirectional"))
    )
    (net (code "35") (name "Net-(LED1-DI)") (class "Default")
      (node (ref "LED1") (pin "4-DIN") (pinfunction "DI_4-DIN") (pintype "input"))
      (node (ref "R_LED_TERM") (pin "1") (pinfunction "1_1") (pintype "passive"))
    )
    (net (code "36") (name "Net-(LED1-DO)") (class "Default")
      (node (ref "LED1") (pin "2-DOUT") (pinfunction "DO_2-DOUT") (pintype "output"))
      (node (ref "LED2") (pin "4-DIN") (pinfunction "DI_4-DIN") (pintype "input"))
    )
    (net (code "37") (name "Net-(LED2-DO)") (class "Default")
      (node (ref "LED2") (pin "2-DOUT") (pinfunction "DO_2-DOUT") (pintype "output"))
      (node (ref "LED3") (pin "4-DIN") (pinfunction "DI_4-DIN") (pintype "input"))
    )
    (net (code "38") (name "Net-(LED3-DO)") (class "Default")
      (node (ref "LED3") (pin "2-DOUT") (pinfunction "DO_2-DOUT") (pintype "output"))
      (node (ref "LED4") (pin "4-DIN") (pinfunction "DI_4-DIN") (pintype "input"))
    )
    (net (code "39") (name "Net-(LED4-DO)") (class "Default")
      (node (ref "LED4") (pin "2-DOUT") (pinfunction "DO_2-DOUT") (pintype "output"))
      (node (ref "LED5") (pin "4-DIN") (pinfunction "DI_4-DIN") (pintype "input"))
    )
    (net (code "40") (name "Net-(LED5-DO)") (class "Default")
      (node (ref "LED5") (pin "2-DOUT") (pinfunction "DO_2-DOUT") (pintype "output"))
      (node (ref "LED6") (pin "4-DIN") (pinfunction "DI_4-DIN") (pintype "input"))
    )
    (net (code "41") (name "Net-(LED6-DO)") (class "Default")
      (node (ref "LED6") (pin "2-DOUT") (pinfunction "DO_2-DOUT") (pintype "output"))
      (node (ref "LED7") (pin "4-DIN") (pinfunction "DI_4-DIN") (pintype "input"))
    )
    (net (code "42") (name "Net-(LED7-DO)") (class "Default")
      (node (ref "LED7") (pin "2-DOUT") (pinfunction "DO_2-DOUT") (pintype "output"))
      (node (ref "LED8") (pin "4-DIN") (pinfunction "DI_4-DIN") (pintype "input"))
    )
    (net (code "43") (name "Net-(LED8-DO)") (class "Default")
      (node (ref "LED8") (pin "2-DOUT") (pinfunction "DO_2-DOUT") (pintype "output"))
      (node (ref "LED9") (pin "4-DIN") (pinfunction "DI_4-DIN") (pintype "input"))
    )
    (net (code "44") (name "Net-(LED10-DI)") (class "Default")
      (node (ref "LED10") (pin "4-DIN") (pinfunction "DI_4-DIN") (pintype "input"))
      (node (ref "LED9") (pin "2-DOUT") (pinfunction "DO_2-DOUT") (pintype "output"))
    )
    (net (code "45") (name "Net-(LED10-DO)") (class "Default")
      (node (ref "LED10") (pin "2-DOUT") (pinfunction "DO_2-DOUT") (pintype "output"))
      (node (ref "LED11") (pin "4-DIN") (pinfunction "DI_4-DIN") (pintype "input"))
    )
    (net (code "46") (name "Net-(LED11-DO)") (class "Default")
      (node (ref "LED11") (pin "2-DOUT") (pinfunction "DO_2-DOUT") (pintype "output"))
      (node (ref "LED12") (pin "4-DIN") (pinfunction "DI_4-DIN") (pintype "input"))
    )
    (net (code "47") (name "Net-(LED12-DO)") (class "Default")
      (node (ref "LED12") (pin "2-DOUT") (pinfunction "DO_2-DOUT") (pintype "output"))
      (node (ref "LED13") (pin "4-DIN") (pinfunction "DI_4-DIN") (pintype "input"))
    )
    (net (code "48") (name "Net-(LED13-DO)") (class "Default")
      (node (ref "LED13") (pin "2-DOUT") (pinfunction "DO_2-DOUT") (pintype "output"))
      (node (ref "LED14") (pin "4-DIN") (pinfunction "DI_4-DIN") (pintype "input"))
    )
    (net (code "49") (name "Net-(LED14-DO)") (class "Default")
      (node (ref "LED14") (pin "2-DOUT") (pinfunction "DO_2-DOUT") (pintype "output"))
      (node (ref "LED15") (pin "4-DIN") (pinfunction "DI_4-DIN") (pintype "input"))
    )
    (net (code "50") (name "Net-(LED15-DO)") (class "Default")
      (node (ref "LED15") (pin "2-DOUT") (pinfunction "DO_2-DOUT") (pintype "output"))
      (node (ref "LED16") (pin "4-DIN") (pinfunction "DI_4-DIN") (pintype "input"))
    )
    (net (code "51") (name "Net-(LED16-DO)") (class "Default")
      (node (ref "LED16") (pin "2-DOUT") (pinfunction "DO_2-DOUT") (pintype "output"))
      (node (ref "LED17") (pin "4-DIN") (pinfunction "DI_4-DIN") (pintype "input"))
    )
    (net (code "52") (name "Net-(LED17-DO)") (class "Default")
      (node (ref "LED17") (pin "2-DOUT") (pinfunction "DO_2-DOUT") (pintype "output"))
      (node (ref "LED18") (pin "4-DIN") (pinfunction "DI_4-DIN") (pintype "input"))
    )
    (net (code "53") (name "Net-(LED18-DO)") (class "Default")
      (node (ref "LED18") (pin "2-DOUT") (pinfunction "DO_2-DOUT") (pintype "output"))
      (node (ref "LED19") (pin "4-DIN") (pinfunction "DI_4-DIN") (pintype "input"))
    )
    (net (code "54") (name "Net-(LED19-DO)") (class "Default")
      (node (ref "LED19") (pin "2-DOUT") (pinfunction "DO_2-DOUT") (pintype "output"))
      (node (ref "LED20") (pin "4-DIN") (pinfunction "DI_4-DIN") (pintype "input"))
    )
    (net (code "55") (name "Net-(LED20-DO)") (class "Default")
      (node (ref "LED20") (pin "2-DOUT") (pinfunction "DO_2-DOUT") (pintype "output"))
      (node (ref "LED21") (pin "4-DIN") (pinfunction "DI_4-DIN") (pintype "input"))
    )
    (net (code "56") (name "Net-(LED21-DO)") (class "Default")
      (node (ref "LED21") (pin "2-DOUT") (pinfunction "DO_2-DOUT") (pintype "output"))
      (node (ref "LED22") (pin "4-DIN") (pinfunction "DI_4-DIN") (pintype "input"))
    )
    (net (code "57") (name "Net-(LED22-DO)") (class "Default")
      (node (ref "LED22") (pin "2-DOUT") (pinfunction "DO_2-DOUT") (pintype "output"))
      (node (ref "LED23") (pin "4-DIN") (pinfunction "DI_4-DIN") (pintype "input"))
    )
    (net (code "58") (name "Net-(LED23-DO)") (class "Default")
      (node (ref "LED23") (pin "2-DOUT") (pinfunction "DO_2-DOUT") (pintype "output"))
      (node (ref "LED24") (pin "4-DIN") (pinfunction "DI_4-DIN") (pintype "input"))
    )
    (net (code "59") (name "Net-(LED24-DO)") (class "Default")
      (node (ref "LED24") (pin "2-DOUT") (pinfunction "DO_2-DOUT") (pintype "output"))
      (node (ref "LED25") (pin "4-DIN") (pinfunction "DI_4-DIN") (pintype "input"))
    )
    (net (code "60") (name "Net-(LED25-DO)") (class "Default")
      (node (ref "LED25") (pin "2-DOUT") (pinfunction "DO_2-DOUT") (pintype "output"))
      (node (ref "LED26") (pin "4-DIN") (pinfunction "DI_4-DIN") (pintype "input"))
    )
    (net (code "61") (name "Net-(LED26-DO)") (class "Default")
      (node (ref "LED26") (pin "2-DOUT") (pinfunction "DO_2-DOUT") (pintype "output"))
      (node (ref "LED27") (pin "4-DIN") (pinfunction "DI_4-DIN") (pintype "input"))
    )
    (net (code "62") (name "Net-(LED27-DO)") (class "Default")
      (node (ref "LED27") (pin "2-DOUT") (pinfunction "DO_2-DOUT") (pintype "output"))
      (node (ref "LED28") (pin "4-DIN") (pinfunction "DI_4-DIN") (pintype "input"))
    )
    (net (code "63") (name "Net-(LED28-DO)") (class "Default")
      (node (ref "LED28") (pin "2-DOUT") (pinfunction "DO_2-DOUT") (pintype "output"))
      (node (ref "LED29") (pin "4-DIN") (pinfunction "DI_4-DIN") (pintype "input"))
    )
    (net (code "64") (name "Net-(LED29-DO)") (class "Default")
      (node (ref "LED29") (pin "2-DOUT") (pinfunction "DO_2-DOUT") (pintype "output"))
      (node (ref "LED30") (pin "4-DIN") (pinfunction "DI_4-DIN") (pintype "input"))
    )
    (net (code "65") (name "Net-(LED30-DO)") (class "Default")
      (node (ref "LED30") (pin "2-DOUT") (pinfunction "DO_2-DOUT") (pintype "output"))
      (node (ref "LED31") (pin "4-DIN") (pinfunction "DI_4-DIN") (pintype "input"))
    )
    (net (code "66") (name "Net-(LED31-DO)") (class "Default")
      (node (ref "LED31") (pin "2-DOUT") (pinfunction "DO_2-DOUT") (pintype "output"))
      (node (ref "LED32") (pin "4-DIN") (pinfunction "DI_4-DIN") (pintype "input"))
    )
    (net (code "67") (name "Net-(LED32-DO)") (class "Default")
      (node (ref "LED32") (pin "2-DOUT") (pinfunction "DO_2-DOUT") (pintype "output"))
      (node (ref "LED33") (pin "4-DIN") (pinfunction "DI_4-DIN") (pintype "input"))
    )
    (net (code "68") (name "Net-(LED33-DO)") (class "Default")
      (node (ref "LED33") (pin "2-DOUT") (pinfunction "DO_2-DOUT") (pintype "output"))
      (node (ref "LED34") (pin "4-DIN") (pinfunction "DI_4-DIN") (pintype "input"))
    )
    (net (code "69") (name "Net-(LED34-DO)") (class "Default")
      (node (ref "LED34") (pin "2-DOUT") (pinfunction "DO_2-DOUT") (pintype "output"))
      (node (ref "LED35") (pin "4-DIN") (pinfunction "DI_4-DIN") (pintype "input"))
    )
    (net (code "70") (name "Net-(LED35-DO)") (class "Default")
      (node (ref "LED35") (pin "2-DOUT") (pinfunction "DO_2-DOUT") (pintype "output"))
      (node (ref "LED36") (pin "4-DIN") (pinfunction "DI_4-DIN") (pintype "input"))
    )
    (net (code "71") (name "Net-(PWR_LED-PadA)") (class "Default")
      (node (ref "PWR_LED") (pin "A") (pinfunction "A_A") (pintype "passive"))
      (node (ref "R_PLED") (pin "1") (pinfunction "1_1") (pintype "passive"))
    )
    (net (code "72") (name "Net-(Q1-G)") (class "Default")
      (node (ref "Q1") (pin "1") (pinfunction "G_1") (pintype "bidirectional"))
      (node (ref "R_LED_EN1") (pin "1") (pinfunction "1_1") (pintype "passive"))
      (node (ref "R_LED_PD1") (pin "2") (pinfunction "2_2") (pintype "passive"))
    )
    (net (code "73") (name "Net-(Q3-X1)") (class "Default")
      (node (ref "C17") (pin "2") (pinfunction "2_2") (pintype "passive"))
      (node (ref "Q3") (pin "1") (pinfunction "X1_1") (pintype "bidirectional"))
      (node (ref "U0") (pin "16") (pinfunction "XTAL2_16") (pintype "bidirectional"))
    )
    (net (code "74") (name "Net-(Q3-X2)") (class "Default")
      (node (ref "C16") (pin "2") (pinfunction "2_2") (pintype "passive"))
      (node (ref "Q3") (pin "3") (pinfunction "X2_3") (pintype "bidirectional"))
      (node (ref "U0") (pin "17") (pinfunction "XTAL1_17") (pintype "bidirectional"))
    )
    (net (code "75") (name "Net-(Q4-D)") (class "Default")
      (node (ref "Q4") (pin "3") (pinfunction "D_3") (pintype "bidirectional"))
      (node (ref "R_LED_EN3") (pin "2") (pinfunction "2_2") (pintype "passive"))
      (node (ref "R_LED_PD3") (pin "1") (pinfunction "1_1") (pintype "passive"))
    )
    (net (code "76") (name "Net-(Q4-G)") (class "Default")
      (node (ref "Q4") (pin "1") (pinfunction "G_1") (pintype "bidirectional"))
      (node (ref "R_COIL_EN") (pin "1") (pinfunction "1_1") (pintype "passive"))
      (node (ref "R_COIL_PD") (pin "2") (pinfunction "2_2") (pintype "passive"))
    )
    (net (code "77") (name "Net-(Q5-G)") (class "Default")
      (node (ref "Q5") (pin "1") (pinfunction "G_1") (pintype "bidirectional"))
      (node (ref "R_LED_EN3") (pin "1") (pinfunction "1_1") (pintype "passive"))
    )
    (net (code "78") (name "Net-(R_LED-Pad1)") (class "Default")
      (node (ref "R_LED") (pin "1") (pinfunction "1_1") (pintype "passive"))
      (node (ref "USER_LED") (pin "A") (pinfunction "A_A") (pintype "passive"))
    )
    (net (code "79") (name "Net-(U0-UCAP)") (class "Default")
      (node (ref "C_UCAP") (pin "1") (pinfunction "1_1") (pintype "passive"))
      (node (ref "U0") (pin "6") (pinfunction "UCAP_6") (pintype "bidirectional"))
    )
    (net (code "80") (name "SCK") (class "Default")
      (node (ref "CORTEX_SWD1") (pin "1") (pinfunction "VCC_1") (pintype "bidirectional"))
      (node (ref "U0") (pin "9") (pinfunction "PB1(SCK)_9") (pintype "bidirectional"))
    )
    (net (code "81") (name "SCL") (class "Default")
      (node (ref "JP1") (pin "2") (pinfunction "2_2") (pintype "passive"))
      (node (ref "R_SCL") (pin "1") (pinfunction "1_1") (pintype "passive"))
      (node (ref "U0") (pin "18") (pinfunction "PD0(SCL)_18") (pintype "bidirectional"))
    )
    (net (code "82") (name "SDA") (class "Default")
      (node (ref "JP1") (pin "3") (pinfunction "3_3") (pintype "passive"))
      (node (ref "R_SDA") (pin "1") (pinfunction "1_1") (pintype "passive"))
      (node (ref "U0") (pin "19") (pinfunction "PD1(SDA)_19") (pintype "bidirectional"))
    )
    (net (code "83") (name "SS_RX") (class "Default")
      (node (ref "JP1") (pin "5") (pinfunction "5_5") (pintype "passive"))
      (node (ref "U0") (pin "32") (pinfunction "PC7_32") (pintype "bidirectional"))
    )
    (net (code "84") (name "SS_TX") (class "Default")
      (node (ref "JP1") (pin "4") (pinfunction "4_4") (pintype "passive"))
      (node (ref "U0") (pin "31") (pinfunction "PC6_31") (pintype "bidirectional"))
    )
    (net (code "85") (name "TMS") (class "Default")
      (node (ref "CORTEX_SWD1") (pin "5") (pinfunction "GND_5") (pintype "bidirectional"))
    )
    (net (code "86") (name "USR_LED") (class "Default")
      (node (ref "R_LED") (pin "2") (pinfunction "2_2") (pintype "passive"))
      (node (ref "U0") (pin "22") (pinfunction "PD5_22") (pintype "bidirectional"))
    )
    (net (code "87") (name "unconnected-(CORTEX_SWD1-KEY-Pad7)") (class "Default")
      (node (ref "CORTEX_SWD1") (pin "7") (pinfunction "KEY_7") (pintype "bidirectional"))
    )
    (net (code "88") (name "unconnected-(J1-PadID)") (class "Default")
      (node (ref "J1") (pin "ID") (pinfunction "ID_ID") (pintype "bidirectional"))
    )
    (net (code "89") (name "unconnected-(LED36-DO-Pad2-DOUT)") (class "Default")
      (node (ref "LED36") (pin "2-DOUT") (pinfunction "DO_2-DOUT") (pintype "output"))
    )
    (net (code "90") (name "unconnected-(U0-AREF-Pad42)") (class "Default")
      (node (ref "U0") (pin "42") (pinfunction "AREF_42") (pintype "bidirectional"))
    )
  )
)
